# Bridge.net
KiCad netlist of a schematic drawn in Altium Designer
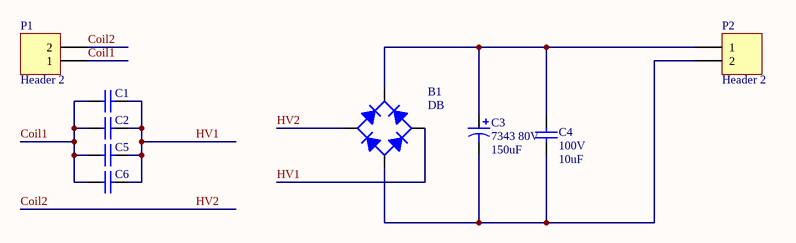
[diagram p0: Bridge.SchDoc]

(export (version "E")
  (design (tool "Eeschema 10.0.6"))
  (components
    (comp (ref "B1")
      (value "DB")
      (footprint "GBU")
      (description "整流桥")
      (fields (field (name "版权归属") "封装库来自淘宝卖家 ID：黄晶宝石"))
      (libsource (lib "0.2 - 二极管-整流桥") (part "DB"))
    )
    (comp (ref "C1")
      (value "Cap")
      (footprint "C1206")
      (description "Capacitor")
      (fields (field (name "PUBLISHER") "Altium Limited"))
      (libsource (lib "Miscellaneous Devices") (part "Cap"))
    )
    (comp (ref "C2")
      (value "Cap")
      (footprint "C1206")
      (description "Capacitor")
      (fields (field (name "PUBLISHER") "Altium Limited"))
      (libsource (lib "Miscellaneous Devices") (part "Cap"))
    )
    (comp (ref "C3")
      (value "7343 80V")
      (footprint "CAP-SMD_BD12.5-L13.0-W13.0-FD")
      (description "Polarized Capacitor (Radial)")
      (fields (field (name "ALTIUM_VALUE") "150uF") (field (name "PUBLISHER") "Altium Limited"))
      (libsource (lib "Miscellaneous Devices") (part "Cap Pol1"))
    )
    (comp (ref "C4")
      (value "100V")
      (footprint "C2220")
      (description "Capacitor")
      (fields (field (name "ALTIUM_VALUE") "10uF") (field (name "PUBLISHER") "Altium Limited"))
      (libsource (lib "Miscellaneous Devices") (part "Cap"))
    )
    (comp (ref "C5")
      (value "Cap")
      (footprint "C1206")
      (description "Capacitor")
      (fields (field (name "PUBLISHER") "Altium Limited"))
      (libsource (lib "Miscellaneous Devices") (part "Cap"))
    )
    (comp (ref "C6")
      (value "Cap")
      (footprint "C1206")
      (description "Capacitor")
      (fields (field (name "PUBLISHER") "Altium Limited"))
      (libsource (lib "Miscellaneous Devices") (part "Cap"))
    )
    (comp (ref "P1")
      (value "Header 2")
      (footprint "2PIN-5.08B")
      (description "Header, 2-Pin")
      (fields (field (name "PUBLISHER") "Altium Limited"))
      (libsource (lib "Miscellaneous Connectors") (part "Header 2"))
    )
    (comp (ref "P2")
      (value "Header 2")
      (footprint "2PIN-5.08B")
      (description "Header, 2-Pin")
      (fields (field (name "PUBLISHER") "Altium Limited"))
      (libsource (lib "") (part "Header 2_1"))
    )
  )
  (nets
    (net (code "1") (name "/Coil1") (class "Default")
      (node (ref "C1") (pin "2") (pinfunction "2_2") (pintype "passive"))
      (node (ref "C2") (pin "2") (pinfunction "2_2") (pintype "passive"))
      (node (ref "C5") (pin "2") (pinfunction "2_2") (pintype "passive"))
      (node (ref "C6") (pin "2") (pinfunction "2_2") (pintype "passive"))
      (node (ref "P1") (pin "1") (pinfunction "1_1") (pintype "passive"))
    )
    (net (code "2") (name "/Coil2") (class "Default")
      (node (ref "B1") (pin "AC1") (pinfunction "AC1_AC1") (pintype "passive"))
      (node (ref "P1") (pin "2") (pinfunction "2_2") (pintype "passive"))
    )
    (net (code "3") (name "/HV1") (class "Default")
      (node (ref "B1") (pin "AC2") (pinfunction "AC2_AC2") (pintype "passive"))
      (node (ref "C1") (pin "1") (pinfunction "1_1") (pintype "passive"))
      (node (ref "C2") (pin "1") (pinfunction "1_1") (pintype "passive"))
      (node (ref "C5") (pin "1") (pinfunction "1_1") (pintype "passive"))
      (node (ref "C6") (pin "1") (pinfunction "1_1") (pintype "passive"))
    )
    (net (code "4") (name "Net-(B1-PadDC+)") (class "Default")
      (node (ref "B1") (pin "DC+") (pinfunction "DC+_DC+") (pintype "passive"))
      (node (ref "C3") (pin "1") (pinfunction "1_1") (pintype "passive"))
      (node (ref "C4") (pin "2") (pinfunction "2_2") (pintype "passive"))
      (node (ref "P2") (pin "1") (pinfunction "1_1") (pintype "passive"))
    )
    (net (code "5") (name "Net-(B1-PadDC-)") (class "Default")
      (node (ref "B1") (pin "DC-") (pinfunction "DC-_DC-") (pintype "passive"))
      (node (ref "C3") (pin "2") (pinfunction "2_2") (pintype "passive"))
      (node (ref "C4") (pin "1") (pinfunction "1_1") (pintype "passive"))
      (node (ref "P2") (pin "2") (pinfunction "2_2") (pintype "passive"))
    )
  )
)
